# 4_324_039__3_3.net
KiCad netlist of a schematic drawn in Altium Designer
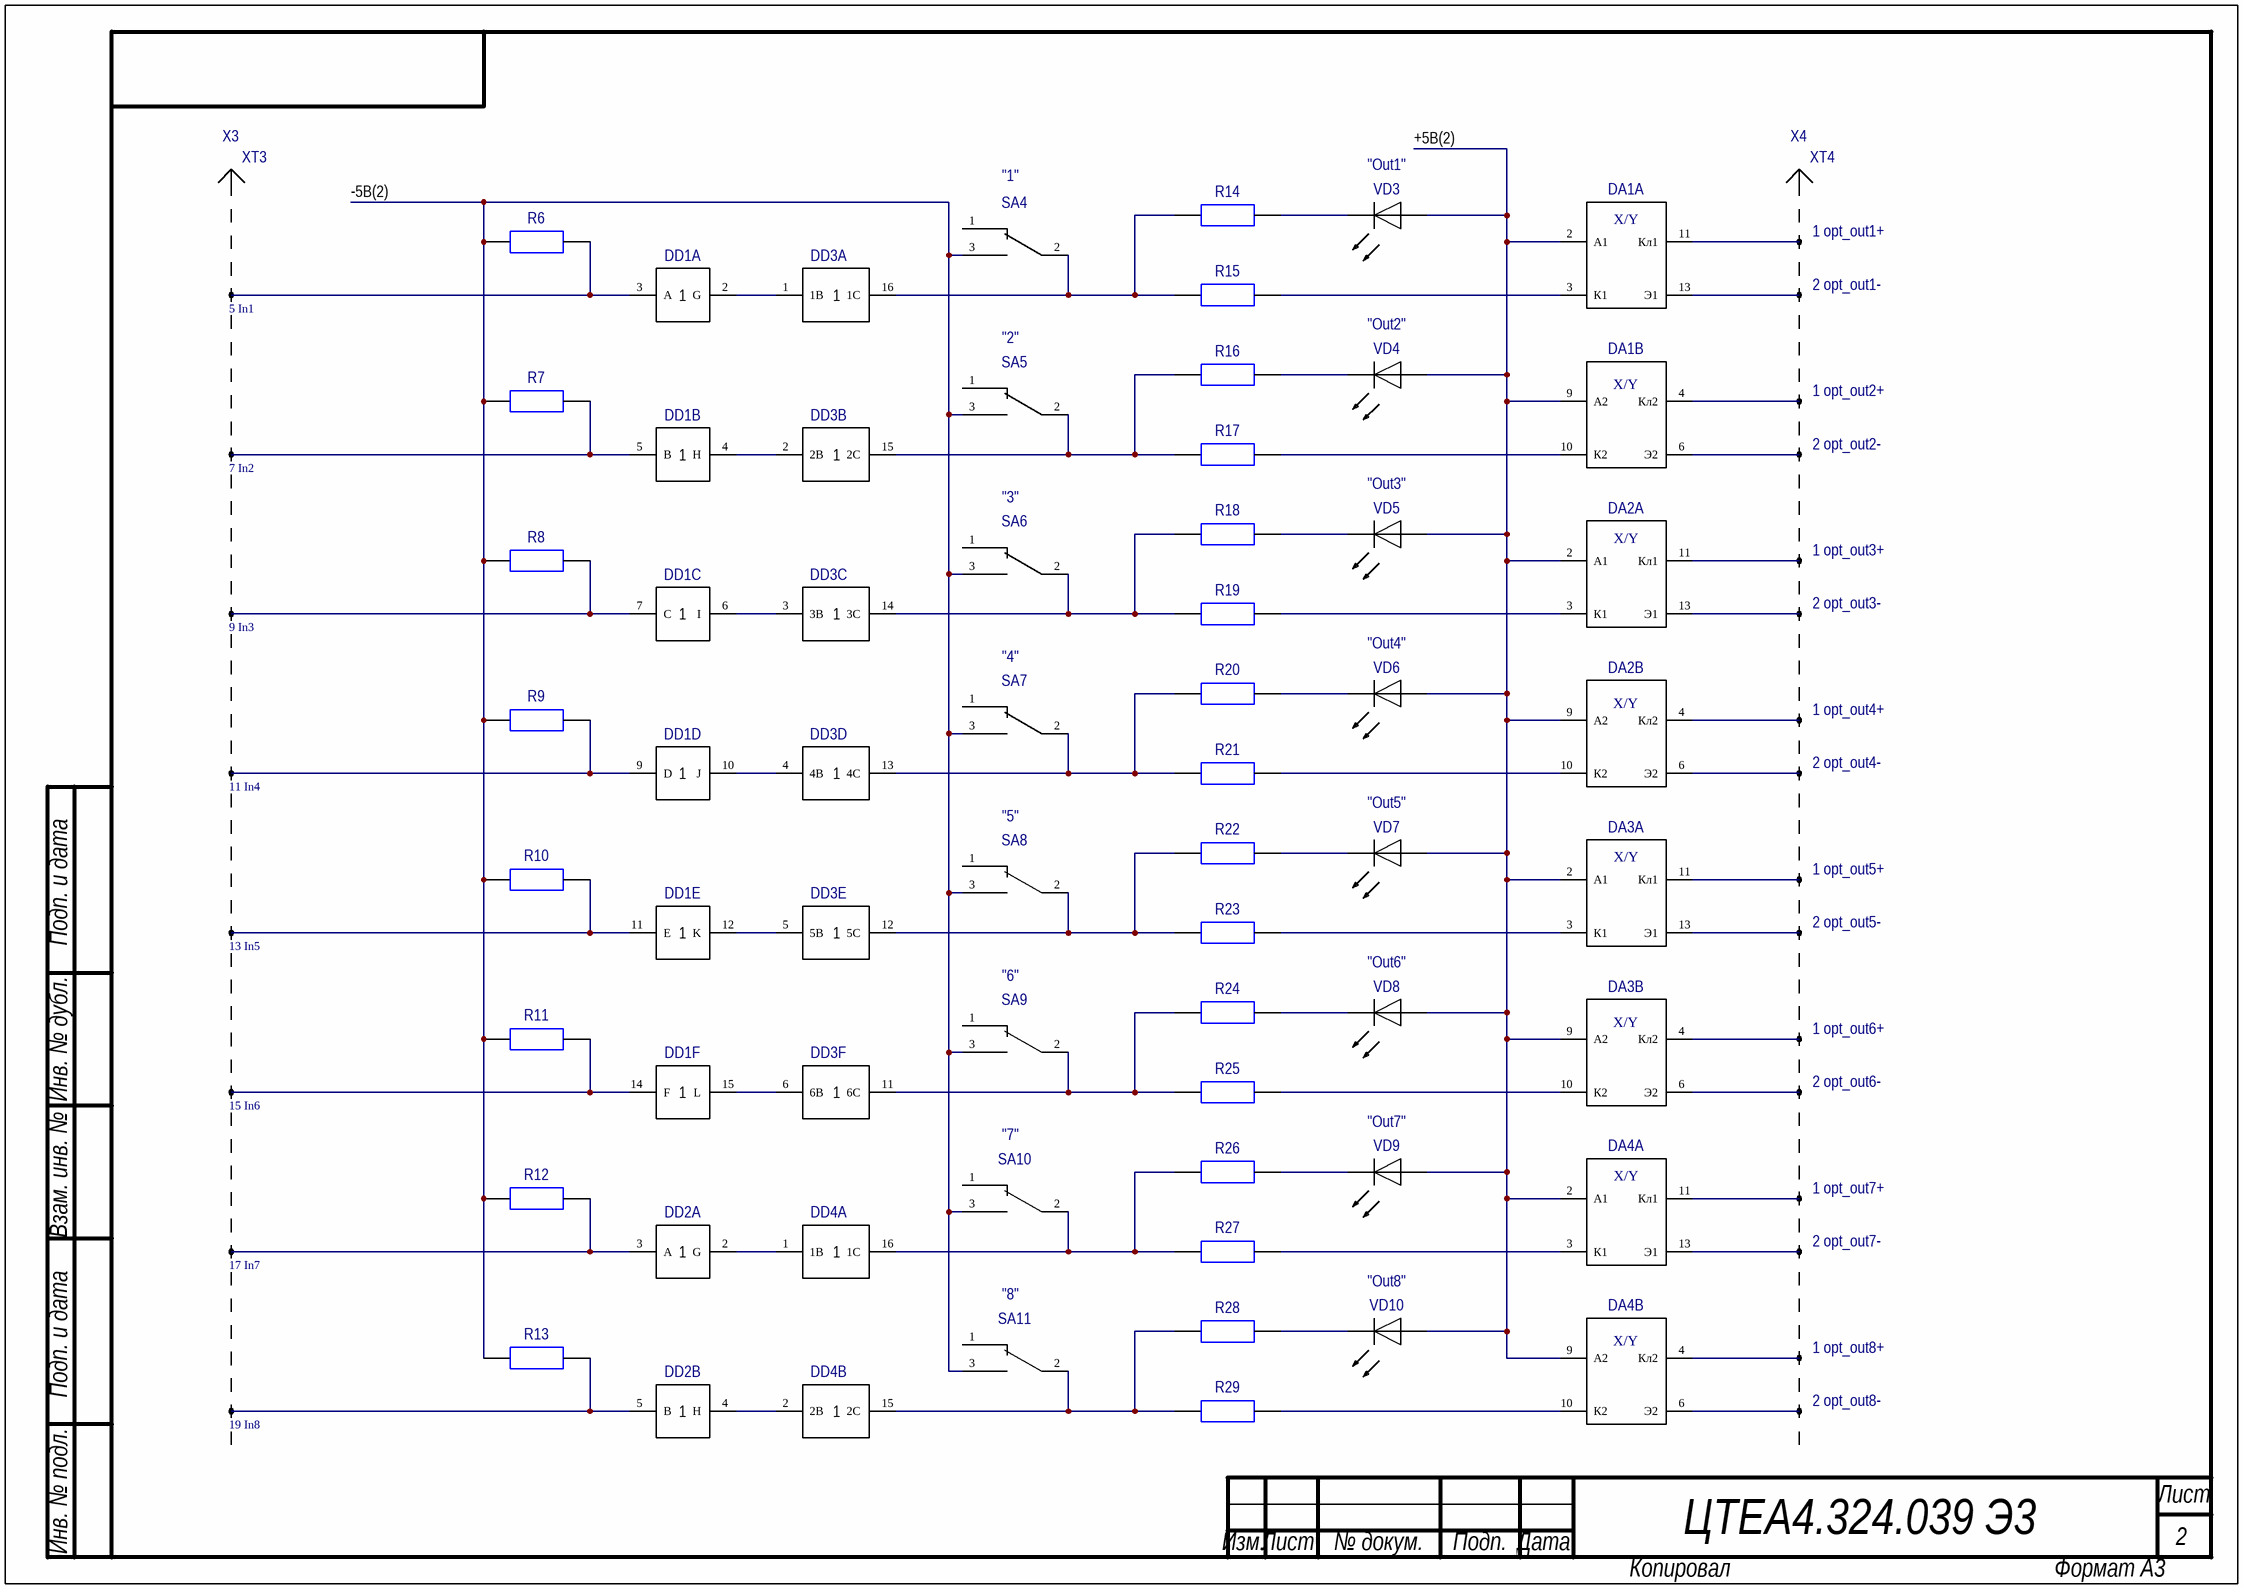
[diagram p0: ЦТЕА4.324.039_Э3_3.SchDoc]

(export (version "E")
  (design (tool "Eeschema 10.0.6"))
  (components
    (comp (ref "DA1")
      (value "249КП1С")
      (footprint "249KP1S_44_3208_125_12-3kl:249KP1S-44_3208_125_12")
      (libsource (lib "249KP1S_44_3208_125_12-3kl") (part "Microshema"))
    )
    (comp (ref "DA2")
      (value "249КП1С")
      (footprint "249KP1S_44_3208_125_12-3kl:249KP1S-44_3208_125_12")
      (libsource (lib "249KP1S_44_3208_125_12-3kl") (part "Microshema"))
    )
    (comp (ref "DA3")
      (value "249КП1С")
      (footprint "249KP1S_44_3208_125_12-3kl:249KP1S-44_3208_125_12")
      (libsource (lib "249KP1S_44_3208_125_12-3kl") (part "Microshema"))
    )
    (comp (ref "DA4")
      (value "249КП1С")
      (footprint "249KP1S_44_3208_125_12-3kl:249KP1S-44_3208_125_12")
      (libsource (lib "249KP1S_44_3208_125_12-3kl") (part "Microshema"))
    )
    (comp (ref "DD1")
      (value "Mikroshema")
      (footprint "CD4050BD")
      (description "CD4050BD")
      (libsource (lib "CD4050BD-3kl") (part "Mikroshema"))
    )
    (comp (ref "DD2")
      (value "Mikroshema")
      (footprint "CD4050BD")
      (description "CD4050BD")
      (libsource (lib "CD4050BD-3kl") (part "Mikroshema"))
    )
    (comp (ref "DD3")
      (value "Mikroshema")
      (footprint "UL2004AD")
      (description "ULN2004")
      (libsource (lib "ULN2004AD-3kl") (part "Mikroshema"))
    )
    (comp (ref "DD4")
      (value "Mikroshema")
      (footprint "UL2004AD")
      (description "ULN2004")
      (libsource (lib "ULN2004AD-3kl") (part "Mikroshema"))
    )
    (comp (ref "R6")
      (value "Res")
      (footprint "CR1206-JW-3301ELF")
      (libsource (lib "CR1206-JW-3301ELF-3kl") (part "Rezistor"))
    )
    (comp (ref "R7")
      (value "Res")
      (footprint "CR1206-JW-3301ELF")
      (libsource (lib "CR1206-JW-3301ELF-3kl") (part "Rezistor"))
    )
    (comp (ref "R8")
      (value "Res")
      (footprint "CR1206-JW-3301ELF")
      (libsource (lib "CR1206-JW-3301ELF-3kl") (part "Rezistor"))
    )
    (comp (ref "R9")
      (value "Res")
      (footprint "CR1206-JW-3301ELF")
      (libsource (lib "CR1206-JW-3301ELF-3kl") (part "Rezistor"))
    )
    (comp (ref "R10")
      (value "Res")
      (footprint "CR1206-JW-3301ELF")
      (libsource (lib "CR1206-JW-3301ELF-3kl") (part "Rezistor"))
    )
    (comp (ref "R11")
      (value "Res")
      (footprint "CR1206-JW-3301ELF")
      (libsource (lib "CR1206-JW-3301ELF-3kl") (part "Rezistor"))
    )
    (comp (ref "R12")
      (value "Res")
      (footprint "CR1206-JW-3301ELF")
      (libsource (lib "CR1206-JW-3301ELF-3kl") (part "Rezistor"))
    )
    (comp (ref "R13")
      (value "Res")
      (footprint "CR1206-JW-3301ELF")
      (libsource (lib "CR1206-JW-3301ELF-3kl") (part "Rezistor"))
    )
    (comp (ref "R14")
      (value "Res")
      (footprint "CR1206-JW-4700ELF")
      (libsource (lib "CR1206-JW-4700ELF-3kl") (part "Rezistor"))
    )
    (comp (ref "R15")
      (value "Res")
      (footprint "CR1206-JW-3300ELF")
      (libsource (lib "CR1206-JW-3300ELF-3kl") (part "Rezistor"))
    )
    (comp (ref "R16")
      (value "Res")
      (footprint "CR1206-JW-4700ELF")
      (libsource (lib "CR1206-JW-4700ELF-3kl") (part "Rezistor"))
    )
    (comp (ref "R17")
      (value "Res")
      (footprint "CR1206-JW-3300ELF")
      (libsource (lib "CR1206-JW-3300ELF-3kl") (part "Rezistor"))
    )
    (comp (ref "R18")
      (value "Res")
      (footprint "CR1206-JW-4700ELF")
      (libsource (lib "CR1206-JW-4700ELF-3kl") (part "Rezistor"))
    )
    (comp (ref "R19")
      (value "Res")
      (footprint "CR1206-JW-3300ELF")
      (libsource (lib "CR1206-JW-3300ELF-3kl") (part "Rezistor"))
    )
    (comp (ref "R20")
      (value "Res")
      (footprint "CR1206-JW-4700ELF")
      (libsource (lib "CR1206-JW-4700ELF-3kl") (part "Rezistor"))
    )
    (comp (ref "R21")
      (value "Res")
      (footprint "CR1206-JW-3300ELF")
      (libsource (lib "CR1206-JW-3300ELF-3kl") (part "Rezistor"))
    )
    (comp (ref "R22")
      (value "Res")
      (footprint "CR1206-JW-4700ELF")
      (libsource (lib "CR1206-JW-4700ELF-3kl") (part "Rezistor"))
    )
    (comp (ref "R23")
      (value "Res")
      (footprint "CR1206-JW-3300ELF")
      (libsource (lib "CR1206-JW-3300ELF-3kl") (part "Rezistor"))
    )
    (comp (ref "R24")
      (value "Res")
      (footprint "CR1206-JW-4700ELF")
      (libsource (lib "CR1206-JW-4700ELF-3kl") (part "Rezistor"))
    )
    (comp (ref "R25")
      (value "Res")
      (footprint "CR1206-JW-3300ELF")
      (libsource (lib "CR1206-JW-3300ELF-3kl") (part "Rezistor"))
    )
    (comp (ref "R26")
      (value "Res")
      (footprint "CR1206-JW-4700ELF")
      (libsource (lib "CR1206-JW-4700ELF-3kl") (part "Rezistor"))
    )
    (comp (ref "R27")
      (value "Res")
      (footprint "CR1206-JW-3300ELF")
      (libsource (lib "CR1206-JW-3300ELF-3kl") (part "Rezistor"))
    )
    (comp (ref "R28")
      (value "Res")
      (footprint "CR1206-JW-4700ELF")
      (libsource (lib "CR1206-JW-4700ELF-3kl") (part "Rezistor"))
    )
    (comp (ref "R29")
      (value "Res")
      (footprint "CR1206-JW-3300ELF")
      (libsource (lib "CR1206-JW-3300ELF-3kl") (part "Rezistor"))
    )
    (comp (ref "SA4")
      (value "\"1\"")
      (footprint "7101SYZQE-3kl:7107SYZQE")
      (libsource (lib "7101SYZQE-3kl") (part "Perekljuchatel"))
    )
    (comp (ref "SA5")
      (value "\"2\"")
      (footprint "7101SYZQE-3kl:7107SYZQE")
      (libsource (lib "7101SYZQE-3kl") (part "Perekljuchatel"))
    )
    (comp (ref "SA6")
      (value "\"3\"")
      (footprint "7101SYZQE-3kl:7107SYZQE")
      (libsource (lib "7101SYZQE-3kl") (part "Perekljuchatel"))
    )
    (comp (ref "SA7")
      (value "\"4\"")
      (footprint "7101SYZQE-3kl:7107SYZQE")
      (libsource (lib "7101SYZQE-3kl") (part "Perekljuchatel"))
    )
    (comp (ref "SA8")
      (value "\"5\"")
      (footprint "7101SYZQE-3kl:7107SYZQE")
      (libsource (lib "7101SYZQE-3kl") (part "Perekljuchatel"))
    )
    (comp (ref "SA9")
      (value "\"6\"")
      (footprint "7101SYZQE-3kl:7107SYZQE")
      (libsource (lib "7101SYZQE-3kl") (part "Perekljuchatel"))
    )
    (comp (ref "SA10")
      (value "\"7\"")
      (footprint "7101SYZQE-3kl:7107SYZQE")
      (libsource (lib "7101SYZQE-3kl") (part "Perekljuchatel"))
    )
    (comp (ref "SA11")
      (value "\"8\"")
      (footprint "7101SYZQE-3kl:7107SYZQE")
      (libsource (lib "7101SYZQE-3kl") (part "Perekljuchatel"))
    )
    (comp (ref "VD3")
      (value "\"Out1\"")
      (footprint "HLMP-D150")
      (libsource (lib "HLMP-D150-3kl") (part "Svetodiod"))
    )
    (comp (ref "VD4")
      (value "\"Out2\"")
      (footprint "HLMP-D150")
      (libsource (lib "HLMP-D150-3kl") (part "Svetodiod"))
    )
    (comp (ref "VD5")
      (value "\"Out3\"")
      (footprint "HLMP-D150")
      (libsource (lib "HLMP-D150-3kl") (part "Svetodiod"))
    )
    (comp (ref "VD6")
      (value "\"Out4\"")
      (footprint "HLMP-D150")
      (libsource (lib "HLMP-D150-3kl") (part "Svetodiod"))
    )
    (comp (ref "VD7")
      (value "\"Out5\"")
      (footprint "HLMP-D150")
      (libsource (lib "HLMP-D150-3kl") (part "Svetodiod"))
    )
    (comp (ref "VD8")
      (value "\"Out6\"")
      (footprint "HLMP-D150")
      (libsource (lib "HLMP-D150-3kl") (part "Svetodiod"))
    )
    (comp (ref "VD9")
      (value "\"Out7\"")
      (footprint "HLMP-D150")
      (libsource (lib "HLMP-D150-3kl") (part "Svetodiod"))
    )
    (comp (ref "VD10")
      (value "\"Out8\"")
      (footprint "HLMP-D150")
      (libsource (lib "HLMP-D150-3kl") (part "Svetodiod"))
    )
    (comp (ref "XT3")
      (value "5 In1")
      (footprint "PLD-40")
      (libsource (lib "PLD-40-3kl") (part "Razem shtyrevoj"))
    )
    (comp (ref "XT4")
      (value "2 opt_out6-")
      (footprint "PLD-18")
      (libsource (lib "PLD-18-3kl") (part "Razem shtyrevoj"))
    )
  )
  (nets
    (net (code "1") (name "/+5V") (class "Default")
      (node (ref "DA1") (pin "2") (pinfunction "А1_2") (pintype "passive"))
      (node (ref "DA1") (pin "9") (pinfunction "А2_9") (pintype "passive"))
      (node (ref "DA2") (pin "2") (pinfunction "А1_2") (pintype "passive"))
      (node (ref "DA2") (pin "9") (pinfunction "А2_9") (pintype "passive"))
      (node (ref "DA3") (pin "2") (pinfunction "А1_2") (pintype "passive"))
      (node (ref "DA3") (pin "9") (pinfunction "А2_9") (pintype "passive"))
      (node (ref "DA4") (pin "2") (pinfunction "А1_2") (pintype "passive"))
      (node (ref "DA4") (pin "9") (pinfunction "А2_9") (pintype "passive"))
      (node (ref "VD10") (pin "1") (pinfunction "A_1") (pintype "passive"))
      (node (ref "VD3") (pin "1") (pinfunction "A_1") (pintype "passive"))
      (node (ref "VD4") (pin "1") (pinfunction "A_1") (pintype "passive"))
      (node (ref "VD5") (pin "1") (pinfunction "A_1") (pintype "passive"))
      (node (ref "VD6") (pin "1") (pinfunction "A_1") (pintype "passive"))
      (node (ref "VD7") (pin "1") (pinfunction "A_1") (pintype "passive"))
      (node (ref "VD8") (pin "1") (pinfunction "A_1") (pintype "passive"))
      (node (ref "VD9") (pin "1") (pinfunction "A_1") (pintype "passive"))
    )
    (net (code "2") (name "/GND") (class "Default")
      (node (ref "R10") (pin "1") (pinfunction "1_1") (pintype "passive"))
      (node (ref "R11") (pin "1") (pinfunction "1_1") (pintype "passive"))
      (node (ref "R12") (pin "1") (pinfunction "1_1") (pintype "passive"))
      (node (ref "R13") (pin "1") (pinfunction "1_1") (pintype "passive"))
      (node (ref "R6") (pin "1") (pinfunction "1_1") (pintype "passive"))
      (node (ref "R7") (pin "1") (pinfunction "1_1") (pintype "passive"))
      (node (ref "R8") (pin "1") (pinfunction "1_1") (pintype "passive"))
      (node (ref "R9") (pin "1") (pinfunction "1_1") (pintype "passive"))
      (node (ref "SA10") (pin "3") (pinfunction "3_3") (pintype "passive"))
      (node (ref "SA11") (pin "3") (pinfunction "3_3") (pintype "passive"))
      (node (ref "SA4") (pin "3") (pinfunction "3_3") (pintype "passive"))
      (node (ref "SA5") (pin "3") (pinfunction "3_3") (pintype "passive"))
      (node (ref "SA6") (pin "3") (pinfunction "3_3") (pintype "passive"))
      (node (ref "SA7") (pin "3") (pinfunction "3_3") (pintype "passive"))
      (node (ref "SA8") (pin "3") (pinfunction "3_3") (pintype "passive"))
      (node (ref "SA9") (pin "3") (pinfunction "3_3") (pintype "passive"))
    )
    (net (code "3") (name "Net-(DA1A-К1)") (class "Default")
      (node (ref "DA1") (pin "3") (pinfunction "К1_3") (pintype "passive"))
      (node (ref "R15") (pin "2") (pinfunction "2_2") (pintype "passive"))
    )
    (net (code "4") (name "Net-(DA1A-Кл1)") (class "Default")
      (node (ref "DA1") (pin "11") (pinfunction "Кл1_11") (pintype "passive"))
      (node (ref "XT4") (pin "1") (pinfunction "1_1") (pintype "passive"))
    )
    (net (code "5") (name "Net-(DA1A-Э1)") (class "Default")
      (node (ref "DA1") (pin "13") (pinfunction "Э1_13") (pintype "passive"))
      (node (ref "XT4") (pin "2") (pinfunction "2_2") (pintype "passive"))
    )
    (net (code "6") (name "Net-(DA1B-К2)") (class "Default")
      (node (ref "DA1") (pin "10") (pinfunction "К2_10") (pintype "passive"))
      (node (ref "R17") (pin "2") (pinfunction "2_2") (pintype "passive"))
    )
    (net (code "7") (name "Net-(DA1B-Кл2)") (class "Default")
      (node (ref "DA1") (pin "4") (pinfunction "Кл2_4") (pintype "passive"))
      (node (ref "XT4") (pin "3") (pinfunction "3_3") (pintype "passive"))
    )
    (net (code "8") (name "Net-(DA1B-Э2)") (class "Default")
      (node (ref "DA1") (pin "6") (pinfunction "Э2_6") (pintype "passive"))
      (node (ref "XT4") (pin "4") (pinfunction "4_4") (pintype "passive"))
    )
    (net (code "9") (name "Net-(DA2A-К1)") (class "Default")
      (node (ref "DA2") (pin "3") (pinfunction "К1_3") (pintype "passive"))
      (node (ref "R19") (pin "2") (pinfunction "2_2") (pintype "passive"))
    )
    (net (code "10") (name "Net-(DA2A-Кл1)") (class "Default")
      (node (ref "DA2") (pin "11") (pinfunction "Кл1_11") (pintype "passive"))
      (node (ref "XT4") (pin "5") (pinfunction "5_5") (pintype "passive"))
    )
    (net (code "11") (name "Net-(DA2A-Э1)") (class "Default")
      (node (ref "DA2") (pin "13") (pinfunction "Э1_13") (pintype "passive"))
      (node (ref "XT4") (pin "6") (pinfunction "6_6") (pintype "passive"))
    )
    (net (code "12") (name "Net-(DA2B-К2)") (class "Default")
      (node (ref "DA2") (pin "10") (pinfunction "К2_10") (pintype "passive"))
      (node (ref "R21") (pin "2") (pinfunction "2_2") (pintype "passive"))
    )
    (net (code "13") (name "Net-(DA2B-Кл2)") (class "Default")
      (node (ref "DA2") (pin "4") (pinfunction "Кл2_4") (pintype "passive"))
      (node (ref "XT4") (pin "7") (pinfunction "7_7") (pintype "passive"))
    )
    (net (code "14") (name "Net-(DA2B-Э2)") (class "Default")
      (node (ref "DA2") (pin "6") (pinfunction "Э2_6") (pintype "passive"))
      (node (ref "XT4") (pin "8") (pinfunction "8_8") (pintype "passive"))
    )
    (net (code "15") (name "Net-(DA3A-К1)") (class "Default")
      (node (ref "DA3") (pin "3") (pinfunction "К1_3") (pintype "passive"))
      (node (ref "R23") (pin "2") (pinfunction "2_2") (pintype "passive"))
    )
    (net (code "16") (name "Net-(DA3A-Кл1)") (class "Default")
      (node (ref "DA3") (pin "11") (pinfunction "Кл1_11") (pintype "passive"))
      (node (ref "XT4") (pin "9") (pinfunction "9_9") (pintype "passive"))
    )
    (net (code "17") (name "Net-(DA3A-Э1)") (class "Default")
      (node (ref "DA3") (pin "13") (pinfunction "Э1_13") (pintype "passive"))
      (node (ref "XT4") (pin "10") (pinfunction "10_10") (pintype "passive"))
    )
    (net (code "18") (name "Net-(DA3B-К2)") (class "Default")
      (node (ref "DA3") (pin "10") (pinfunction "К2_10") (pintype "passive"))
      (node (ref "R25") (pin "2") (pinfunction "2_2") (pintype "passive"))
    )
    (net (code "19") (name "Net-(DA3B-Кл2)") (class "Default")
      (node (ref "DA3") (pin "4") (pinfunction "Кл2_4") (pintype "passive"))
      (node (ref "XT4") (pin "11") (pinfunction "11_11") (pintype "passive"))
    )
    (net (code "20") (name "Net-(DA3B-Э2)") (class "Default")
      (node (ref "DA3") (pin "6") (pinfunction "Э2_6") (pintype "passive"))
      (node (ref "XT4") (pin "12") (pinfunction "12_12") (pintype "passive"))
    )
    (net (code "21") (name "Net-(DA4A-К1)") (class "Default")
      (node (ref "DA4") (pin "3") (pinfunction "К1_3") (pintype "passive"))
      (node (ref "R27") (pin "2") (pinfunction "2_2") (pintype "passive"))
    )
    (net (code "22") (name "Net-(DA4A-Кл1)") (class "Default")
      (node (ref "DA4") (pin "11") (pinfunction "Кл1_11") (pintype "passive"))
      (node (ref "XT4") (pin "13") (pinfunction "13_13") (pintype "passive"))
    )
    (net (code "23") (name "Net-(DA4A-Э1)") (class "Default")
      (node (ref "DA4") (pin "13") (pinfunction "Э1_13") (pintype "passive"))
      (node (ref "XT4") (pin "14") (pinfunction "14_14") (pintype "passive"))
    )
    (net (code "24") (name "Net-(DA4B-К2)") (class "Default")
      (node (ref "DA4") (pin "10") (pinfunction "К2_10") (pintype "passive"))
      (node (ref "R29") (pin "2") (pinfunction "2_2") (pintype "passive"))
    )
    (net (code "25") (name "Net-(DA4B-Кл2)") (class "Default")
      (node (ref "DA4") (pin "4") (pinfunction "Кл2_4") (pintype "passive"))
      (node (ref "XT4") (pin "15") (pinfunction "15_15") (pintype "passive"))
    )
    (net (code "26") (name "Net-(DA4B-Э2)") (class "Default")
      (node (ref "DA4") (pin "6") (pinfunction "Э2_6") (pintype "passive"))
      (node (ref "XT4") (pin "16") (pinfunction "16_16") (pintype "passive"))
    )
    (net (code "27") (name "Net-(DD1A-A)") (class "Default")
      (node (ref "DD1") (pin "3") (pinfunction "A_3") (pintype "passive"))
      (node (ref "R6") (pin "2") (pinfunction "2_2") (pintype "passive"))
      (node (ref "XT3") (pin "5") (pinfunction "5_5") (pintype "passive"))
    )
    (net (code "28") (name "Net-(DD1A-G)") (class "Default")
      (node (ref "DD1") (pin "2") (pinfunction "G_2") (pintype "passive"))
      (node (ref "DD3") (pin "1") (pinfunction "1B_1") (pintype "passive"))
    )
    (net (code "29") (name "Net-(DD1B-B)") (class "Default")
      (node (ref "DD1") (pin "5") (pinfunction "B_5") (pintype "passive"))
      (node (ref "R7") (pin "2") (pinfunction "2_2") (pintype "passive"))
      (node (ref "XT3") (pin "7") (pinfunction "7_7") (pintype "passive"))
    )
    (net (code "30") (name "Net-(DD1B-H)") (class "Default")
      (node (ref "DD1") (pin "4") (pinfunction "H_4") (pintype "passive"))
      (node (ref "DD3") (pin "2") (pinfunction "2B_2") (pintype "passive"))
    )
    (net (code "31") (name "Net-(DD1C-C)") (class "Default")
      (node (ref "DD1") (pin "7") (pinfunction "C_7") (pintype "passive"))
      (node (ref "R8") (pin "2") (pinfunction "2_2") (pintype "passive"))
      (node (ref "XT3") (pin "9") (pinfunction "9_9") (pintype "passive"))
    )
    (net (code "32") (name "Net-(DD1C-I)") (class "Default")
      (node (ref "DD1") (pin "6") (pinfunction "I_6") (pintype "passive"))
      (node (ref "DD3") (pin "3") (pinfunction "3B_3") (pintype "passive"))
    )
    (net (code "33") (name "Net-(DD1D-D)") (class "Default")
      (node (ref "DD1") (pin "9") (pinfunction "D_9") (pintype "passive"))
      (node (ref "R9") (pin "2") (pinfunction "2_2") (pintype "passive"))
      (node (ref "XT3") (pin "11") (pinfunction "11_11") (pintype "passive"))
    )
    (net (code "34") (name "Net-(DD1D-J)") (class "Default")
      (node (ref "DD1") (pin "10") (pinfunction "J_10") (pintype "passive"))
      (node (ref "DD3") (pin "4") (pinfunction "4B_4") (pintype "passive"))
    )
    (net (code "35") (name "Net-(DD1E-E)") (class "Default")
      (node (ref "DD1") (pin "11") (pinfunction "E_11") (pintype "passive"))
      (node (ref "R10") (pin "2") (pinfunction "2_2") (pintype "passive"))
      (node (ref "XT3") (pin "13") (pinfunction "13_13") (pintype "passive"))
    )
    (net (code "36") (name "Net-(DD1E-K)") (class "Default")
      (node (ref "DD1") (pin "12") (pinfunction "K_12") (pintype "passive"))
      (node (ref "DD3") (pin "5") (pinfunction "5B_5") (pintype "passive"))
    )
    (net (code "37") (name "Net-(DD1F-F)") (class "Default")
      (node (ref "DD1") (pin "14") (pinfunction "F_14") (pintype "passive"))
      (node (ref "R11") (pin "2") (pinfunction "2_2") (pintype "passive"))
      (node (ref "XT3") (pin "15") (pinfunction "15_15") (pintype "passive"))
    )
    (net (code "38") (name "Net-(DD1F-L)") (class "Default")
      (node (ref "DD1") (pin "15") (pinfunction "L_15") (pintype "passive"))
      (node (ref "DD3") (pin "6") (pinfunction "6B_6") (pintype "passive"))
    )
    (net (code "39") (name "Net-(DD2A-A)") (class "Default")
      (node (ref "DD2") (pin "3") (pinfunction "A_3") (pintype "passive"))
      (node (ref "R12") (pin "2") (pinfunction "2_2") (pintype "passive"))
      (node (ref "XT3") (pin "17") (pinfunction "17_17") (pintype "passive"))
    )
    (net (code "40") (name "Net-(DD2A-G)") (class "Default")
      (node (ref "DD2") (pin "2") (pinfunction "G_2") (pintype "passive"))
      (node (ref "DD4") (pin "1") (pinfunction "1B_1") (pintype "passive"))
    )
    (net (code "41") (name "Net-(DD2B-B)") (class "Default")
      (node (ref "DD2") (pin "5") (pinfunction "B_5") (pintype "passive"))
      (node (ref "R13") (pin "2") (pinfunction "2_2") (pintype "passive"))
      (node (ref "XT3") (pin "19") (pinfunction "19_19") (pintype "passive"))
    )
    (net (code "42") (name "Net-(DD2B-H)") (class "Default")
      (node (ref "DD2") (pin "4") (pinfunction "H_4") (pintype "passive"))
      (node (ref "DD4") (pin "2") (pinfunction "2B_2") (pintype "passive"))
    )
    (net (code "43") (name "Net-(DD3A-1C)") (class "Default")
      (node (ref "DD3") (pin "16") (pinfunction "1C_16") (pintype "passive"))
      (node (ref "R14") (pin "1") (pinfunction "1_1") (pintype "passive"))
      (node (ref "R15") (pin "1") (pinfunction "1_1") (pintype "passive"))
      (node (ref "SA4") (pin "2") (pinfunction "2_2") (pintype "passive"))
    )
    (net (code "44") (name "Net-(DD3B-2C)") (class "Default")
      (node (ref "DD3") (pin "15") (pinfunction "2C_15") (pintype "passive"))
      (node (ref "R16") (pin "1") (pinfunction "1_1") (pintype "passive"))
      (node (ref "R17") (pin "1") (pinfunction "1_1") (pintype "passive"))
      (node (ref "SA5") (pin "2") (pinfunction "2_2") (pintype "passive"))
    )
    (net (code "45") (name "Net-(DD3C-3C)") (class "Default")
      (node (ref "DD3") (pin "14") (pinfunction "3C_14") (pintype "passive"))
      (node (ref "R18") (pin "1") (pinfunction "1_1") (pintype "passive"))
      (node (ref "R19") (pin "1") (pinfunction "1_1") (pintype "passive"))
      (node (ref "SA6") (pin "2") (pinfunction "2_2") (pintype "passive"))
    )
    (net (code "46") (name "Net-(DD3D-4C)") (class "Default")
      (node (ref "DD3") (pin "13") (pinfunction "4C_13") (pintype "passive"))
      (node (ref "R20") (pin "1") (pinfunction "1_1") (pintype "passive"))
      (node (ref "R21") (pin "1") (pinfunction "1_1") (pintype "passive"))
      (node (ref "SA7") (pin "2") (pinfunction "2_2") (pintype "passive"))
    )
    (net (code "47") (name "Net-(DD3E-5C)") (class "Default")
      (node (ref "DD3") (pin "12") (pinfunction "5C_12") (pintype "passive"))
      (node (ref "R22") (pin "1") (pinfunction "1_1") (pintype "passive"))
      (node (ref "R23") (pin "1") (pinfunction "1_1") (pintype "passive"))
      (node (ref "SA8") (pin "2") (pinfunction "2_2") (pintype "passive"))
    )
    (net (code "48") (name "Net-(DD3F-6C)") (class "Default")
      (node (ref "DD3") (pin "11") (pinfunction "6C_11") (pintype "passive"))
      (node (ref "R24") (pin "1") (pinfunction "1_1") (pintype "passive"))
      (node (ref "R25") (pin "1") (pinfunction "1_1") (pintype "passive"))
      (node (ref "SA9") (pin "2") (pinfunction "2_2") (pintype "passive"))
    )
    (net (code "49") (name "Net-(DD4A-1C)") (class "Default")
      (node (ref "DD4") (pin "16") (pinfunction "1C_16") (pintype "passive"))
      (node (ref "R26") (pin "1") (pinfunction "1_1") (pintype "passive"))
      (node (ref "R27") (pin "1") (pinfunction "1_1") (pintype "passive"))
      (node (ref "SA10") (pin "2") (pinfunction "2_2") (pintype "passive"))
    )
    (net (code "50") (name "Net-(DD4B-2C)") (class "Default")
      (node (ref "DD4") (pin "15") (pinfunction "2C_15") (pintype "passive"))
      (node (ref "R28") (pin "1") (pinfunction "1_1") (pintype "passive"))
      (node (ref "R29") (pin "1") (pinfunction "1_1") (pintype "passive"))
      (node (ref "SA11") (pin "2") (pinfunction "2_2") (pintype "passive"))
    )
    (net (code "51") (name "Net-(VD3-C)") (class "Default")
      (node (ref "R14") (pin "2") (pinfunction "2_2") (pintype "passive"))
      (node (ref "VD3") (pin "2") (pinfunction "C_2") (pintype "passive"))
    )
    (net (code "52") (name "Net-(VD4-C)") (class "Default")
      (node (ref "R16") (pin "2") (pinfunction "2_2") (pintype "passive"))
      (node (ref "VD4") (pin "2") (pinfunction "C_2") (pintype "passive"))
    )
    (net (code "53") (name "Net-(VD5-C)") (class "Default")
      (node (ref "R18") (pin "2") (pinfunction "2_2") (pintype "passive"))
      (node (ref "VD5") (pin "2") (pinfunction "C_2") (pintype "passive"))
    )
    (net (code "54") (name "Net-(VD6-C)") (class "Default")
      (node (ref "R20") (pin "2") (pinfunction "2_2") (pintype "passive"))
      (node (ref "VD6") (pin "2") (pinfunction "C_2") (pintype "passive"))
    )
    (net (code "55") (name "Net-(VD7-C)") (class "Default")
      (node (ref "R22") (pin "2") (pinfunction "2_2") (pintype "passive"))
      (node (ref "VD7") (pin "2") (pinfunction "C_2") (pintype "passive"))
    )
    (net (code "56") (name "Net-(VD8-C)") (class "Default")
      (node (ref "R24") (pin "2") (pinfunction "2_2") (pintype "passive"))
      (node (ref "VD8") (pin "2") (pinfunction "C_2") (pintype "passive"))
    )
    (net (code "57") (name "Net-(VD9-C)") (class "Default")
      (node (ref "R26") (pin "2") (pinfunction "2_2") (pintype "passive"))
      (node (ref "VD9") (pin "2") (pinfunction "C_2") (pintype "passive"))
    )
    (net (code "58") (name "Net-(VD10-C)") (class "Default")
      (node (ref "R28") (pin "2") (pinfunction "2_2") (pintype "passive"))
      (node (ref "VD10") (pin "2") (pinfunction "C_2") (pintype "passive"))
    )
    (net (code "59") (name "unconnected-(SA4-Pad1)") (class "Default")
      (node (ref "SA4") (pin "1") (pinfunction "1_1") (pintype "passive"))
    )
    (net (code "60") (name "unconnected-(SA5-Pad1)") (class "Default")
      (node (ref "SA5") (pin "1") (pinfunction "1_1") (pintype "passive"))
    )
    (net (code "61") (name "unconnected-(SA6-Pad1)") (class "Default")
      (node (ref "SA6") (pin "1") (pinfunction "1_1") (pintype "passive"))
    )
    (net (code "62") (name "unconnected-(SA7-Pad1)") (class "Default")
      (node (ref "SA7") (pin "1") (pinfunction "1_1") (pintype "passive"))
    )
    (net (code "63") (name "unconnected-(SA8-Pad1)") (class "Default")
      (node (ref "SA8") (pin "1") (pinfunction "1_1") (pintype "passive"))
    )
    (net (code "64") (name "unconnected-(SA9-Pad1)") (class "Default")
      (node (ref "SA9") (pin "1") (pinfunction "1_1") (pintype "passive"))
    )
    (net (code "65") (name "unconnected-(SA10-Pad1)") (class "Default")
      (node (ref "SA10") (pin "1") (pinfunction "1_1") (pintype "passive"))
    )
    (net (code "66") (name "unconnected-(SA11-Pad1)") (class "Default")
      (node (ref "SA11") (pin "1") (pinfunction "1_1") (pintype "passive"))
    )
  )
)
